# K3NG_Rotator_Interface_V2.net
KiCad netlist of a schematic drawn in EAGLE
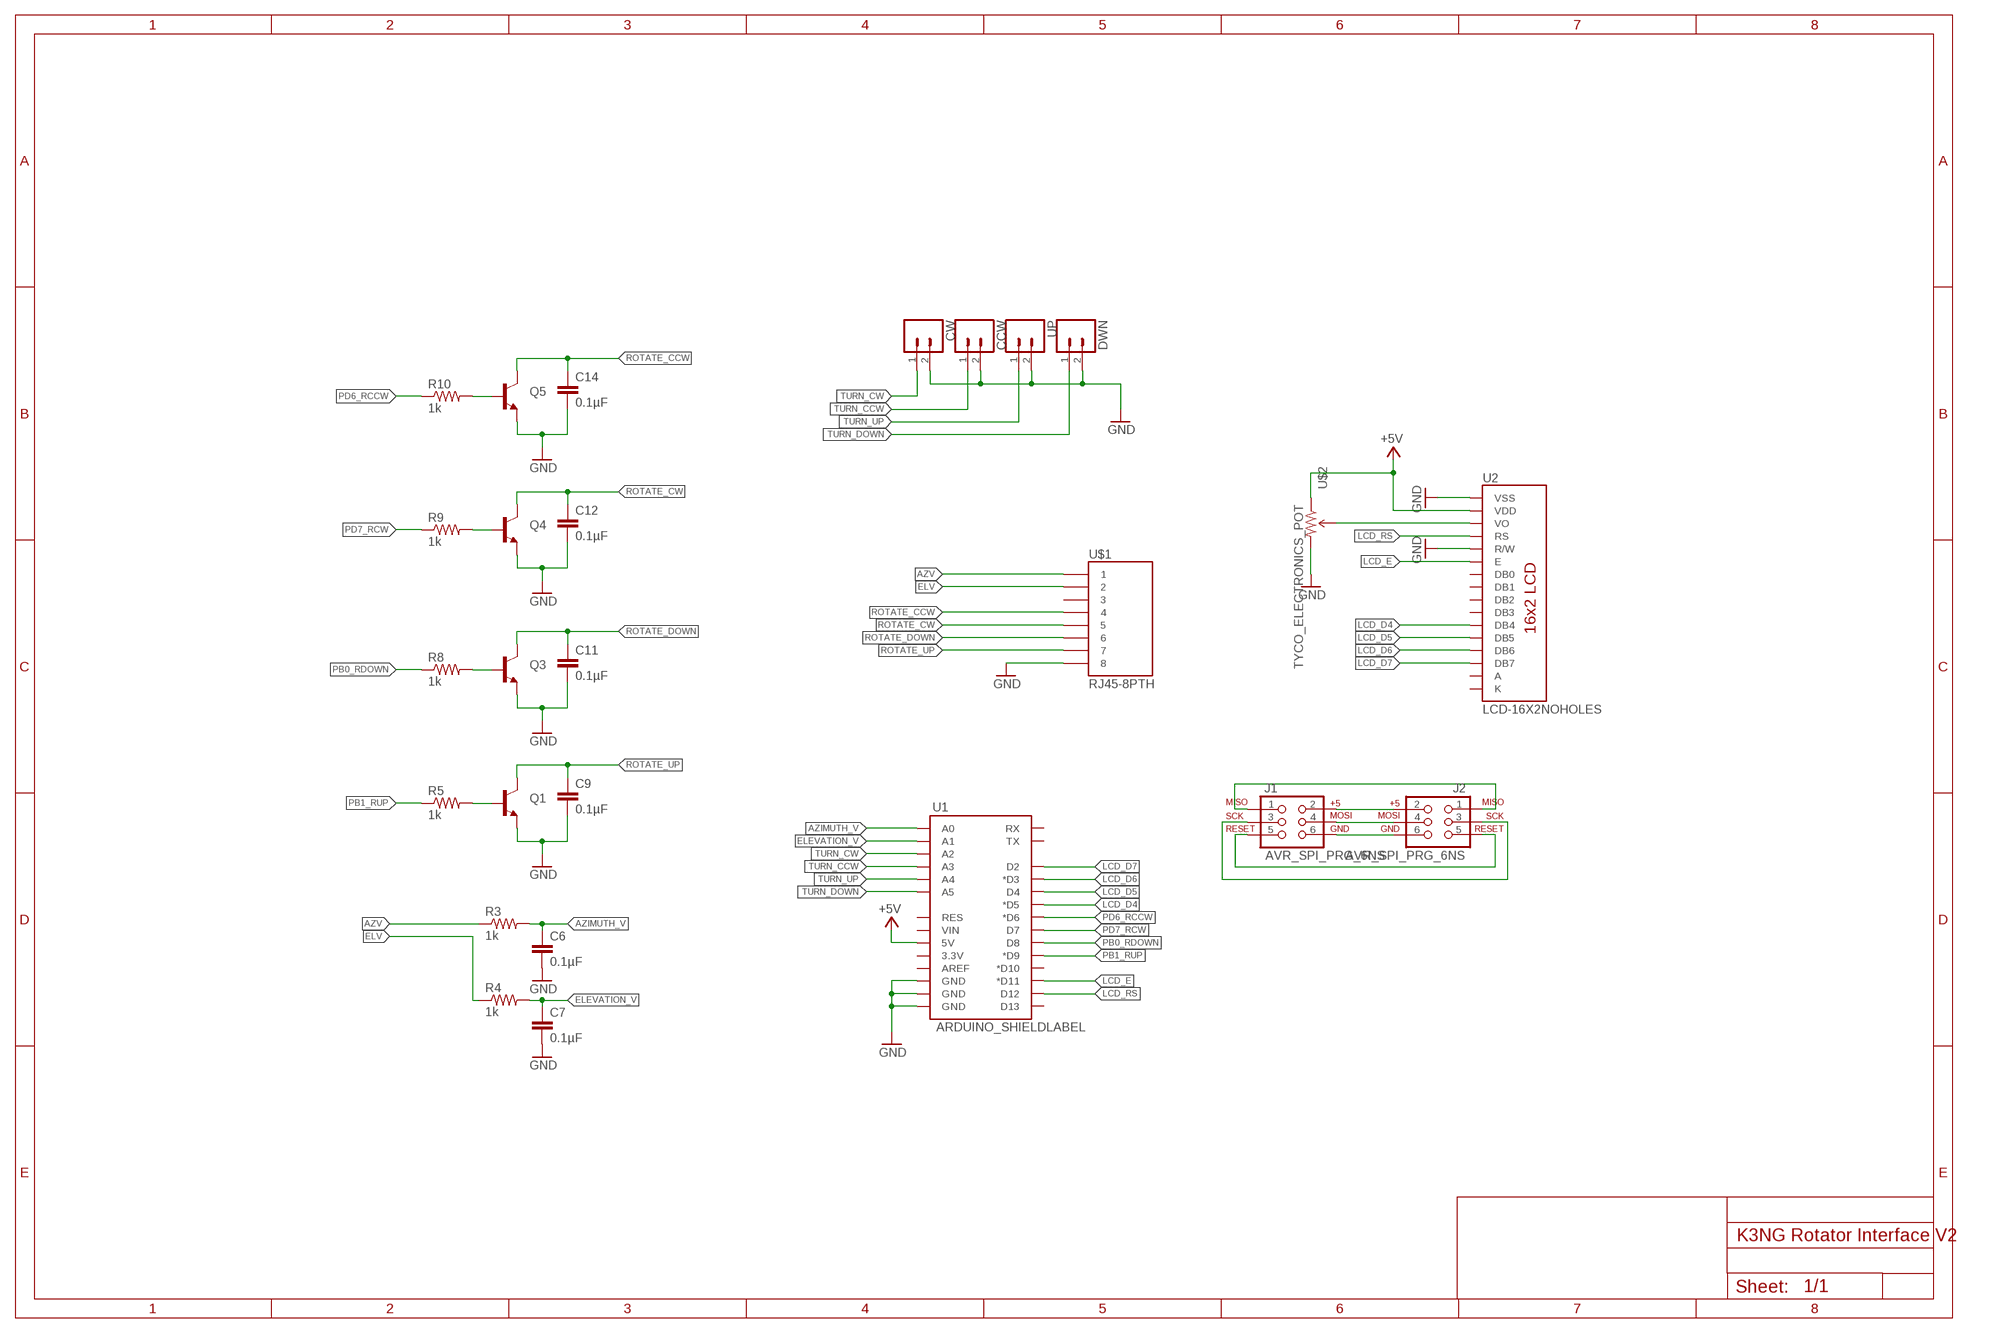
[diagram p0: schematic, sheet 1]

(export (version "E")
  (design (tool "Eeschema 10.0.6"))
  (components
    (comp (ref "C6")
      (value "0.1µF")
      (footprint "eagle-import:0603-CAP")
      (libsource (lib "eagle-import") (part "CAP0603-CAP"))
    )
    (comp (ref "C7")
      (value "0.1µF")
      (footprint "eagle-import:0603-CAP")
      (libsource (lib "eagle-import") (part "CAP0603-CAP"))
    )
    (comp (ref "C9")
      (value "0.1µF")
      (footprint "eagle-import:0603-CAP")
      (libsource (lib "eagle-import") (part "CAP0603-CAP"))
    )
    (comp (ref "C11")
      (value "0.1µF")
      (footprint "eagle-import:0603-CAP")
      (libsource (lib "eagle-import") (part "CAP0603-CAP"))
    )
    (comp (ref "C12")
      (value "0.1µF")
      (footprint "eagle-import:0603-CAP")
      (libsource (lib "eagle-import") (part "CAP0603-CAP"))
    )
    (comp (ref "C14")
      (value "0.1µF")
      (footprint "eagle-import:0603-CAP")
      (libsource (lib "eagle-import") (part "CAP0603-CAP"))
    )
    (comp (ref "CCW")
      (value "M02PTH")
      (footprint "eagle-import:1X02")
      (libsource (lib "eagle-import") (part "M02PTH"))
    )
    (comp (ref "CW")
      (value "M02PTH")
      (footprint "eagle-import:1X02")
      (libsource (lib "eagle-import") (part "M02PTH"))
    )
    (comp (ref "DWN")
      (value "M02PTH")
      (footprint "eagle-import:1X02")
      (libsource (lib "eagle-import") (part "M02PTH"))
    )
    (comp (ref "J1")
      (value "AVR_SPI_PRG_6NS")
      (footprint "eagle-import:2X3-NS")
      (libsource (lib "eagle-import") (part "AVR_SPI_PRG_6NS"))
    )
    (comp (ref "J2")
      (value "AVR_SPI_PRG_6NS")
      (footprint "eagle-import:2X3-NS")
      (libsource (lib "eagle-import") (part "AVR_SPI_PRG_6NS"))
    )
    (comp (ref "Q1")
      (value "TRANSISTOR_NPNSOT23")
      (footprint "eagle-import:SOT23")
      (libsource (lib "eagle-import") (part "TRANSISTOR_NPNSOT23"))
    )
    (comp (ref "Q3")
      (value "TRANSISTOR_NPNSOT23")
      (footprint "eagle-import:SOT23")
      (libsource (lib "eagle-import") (part "TRANSISTOR_NPNSOT23"))
    )
    (comp (ref "Q4")
      (value "TRANSISTOR_NPNSOT23")
      (footprint "eagle-import:SOT23")
      (libsource (lib "eagle-import") (part "TRANSISTOR_NPNSOT23"))
    )
    (comp (ref "Q5")
      (value "TRANSISTOR_NPNSOT23")
      (footprint "eagle-import:SOT23")
      (libsource (lib "eagle-import") (part "TRANSISTOR_NPNSOT23"))
    )
    (comp (ref "R3")
      (value "1k")
      (footprint "eagle-import:0805")
      (libsource (lib "eagle-import") (part "RESISTOR0805-RES"))
    )
    (comp (ref "R4")
      (value "1k")
      (footprint "eagle-import:0805")
      (libsource (lib "eagle-import") (part "RESISTOR0805-RES"))
    )
    (comp (ref "R5")
      (value "1k")
      (footprint "eagle-import:0805")
      (libsource (lib "eagle-import") (part "RESISTOR0805-RES"))
    )
    (comp (ref "R8")
      (value "1k")
      (footprint "eagle-import:0805")
      (libsource (lib "eagle-import") (part "RESISTOR0805-RES"))
    )
    (comp (ref "R9")
      (value "1k")
      (footprint "eagle-import:0805")
      (libsource (lib "eagle-import") (part "RESISTOR0805-RES"))
    )
    (comp (ref "R10")
      (value "1k")
      (footprint "eagle-import:0805")
      (libsource (lib "eagle-import") (part "RESISTOR0805-RES"))
    )
    (comp (ref "U$1")
      (value "RJ45-8PTH")
      (footprint "eagle-import:RJ45-8")
      (libsource (lib "eagle-import") (part "RJ45-8PTH"))
    )
    (comp (ref "U$2")
      (value "TYCO_ELECTRONICS_POT")
      (footprint "eagle-import:TYCO_ELECTRONICS_POT")
      (libsource (lib "eagle-import") (part "TYCO_ELECTRONICS_POT"))
    )
    (comp (ref "U1")
      (value "ARDUINO_SHIELDLABEL")
      (footprint "eagle-import:DUEMILANOVE_SHIELD")
      (libsource (lib "eagle-import") (part "ARDUINO_SHIELDLABEL"))
    )
    (comp (ref "U2")
      (value "LCD-16X2NOHOLES")
      (footprint "eagle-import:LCD-16X2_NOHOLES")
      (libsource (lib "eagle-import") (part "LCD-16X2NOHOLES"))
    )
    (comp (ref "UP")
      (value "M02PTH")
      (footprint "eagle-import:1X02")
      (libsource (lib "eagle-import") (part "M02PTH"))
    )
  )
  (nets
    (net (code "1") (name "+5V") (class "Default")
      (node (ref "U$2") (pin "P$1") (pinfunction "CCW_P$1") (pintype "passive"))
      (node (ref "U1") (pin "5V") (pinfunction "5V_5V") (pintype "bidirectional"))
      (node (ref "U2") (pin "2") (pinfunction "VDD_2") (pintype "power_in"))
    )
    (net (code "2") (name "/A") (class "Default")
      (node (ref "U2") (pin "15") (pinfunction "A_15") (pintype "power_in"))
    )
    (net (code "3") (name "/K") (class "Default")
      (node (ref "U2") (pin "16") (pinfunction "K_16") (pintype "power_in"))
    )
    (net (code "4") (name "AZIMUTH_V") (class "Default")
      (node (ref "C6") (pin "1") (pinfunction "1_1") (pintype "passive"))
      (node (ref "R3") (pin "2") (pinfunction "2_2") (pintype "passive"))
      (node (ref "U1") (pin "A0") (pinfunction "A0_A0") (pintype "bidirectional"))
    )
    (net (code "5") (name "AZV") (class "Default")
      (node (ref "R3") (pin "1") (pinfunction "1_1") (pintype "passive"))
      (node (ref "U$1") (pin "1") (pinfunction "1_1") (pintype "bidirectional"))
    )
    (net (code "6") (name "ELEVATION_V") (class "Default")
      (node (ref "C7") (pin "1") (pinfunction "1_1") (pintype "passive"))
      (node (ref "R4") (pin "2") (pinfunction "2_2") (pintype "passive"))
      (node (ref "U1") (pin "A1") (pinfunction "A1_A1") (pintype "bidirectional"))
    )
    (net (code "7") (name "ELV") (class "Default")
      (node (ref "R4") (pin "1") (pinfunction "1_1") (pintype "passive"))
      (node (ref "U$1") (pin "2") (pinfunction "2_2") (pintype "bidirectional"))
    )
    (net (code "8") (name "GND") (class "Default")
      (node (ref "C11") (pin "2") (pinfunction "2_2") (pintype "passive"))
      (node (ref "C12") (pin "2") (pinfunction "2_2") (pintype "passive"))
      (node (ref "C14") (pin "2") (pinfunction "2_2") (pintype "passive"))
      (node (ref "C6") (pin "2") (pinfunction "2_2") (pintype "passive"))
      (node (ref "C7") (pin "2") (pinfunction "2_2") (pintype "passive"))
      (node (ref "C9") (pin "2") (pinfunction "2_2") (pintype "passive"))
      (node (ref "CCW") (pin "2") (pinfunction "2_2") (pintype "passive"))
      (node (ref "CW") (pin "2") (pinfunction "2_2") (pintype "passive"))
      (node (ref "DWN") (pin "2") (pinfunction "2_2") (pintype "passive"))
      (node (ref "Q1") (pin "2") (pinfunction "E_2") (pintype "passive"))
      (node (ref "Q3") (pin "2") (pinfunction "E_2") (pintype "passive"))
      (node (ref "Q4") (pin "2") (pinfunction "E_2") (pintype "passive"))
      (node (ref "Q5") (pin "2") (pinfunction "E_2") (pintype "passive"))
      (node (ref "U$1") (pin "8") (pinfunction "8_8") (pintype "bidirectional"))
      (node (ref "U$2") (pin "P$3") (pinfunction "CW_P$3") (pintype "passive"))
      (node (ref "U1") (pin "GND@0") (pinfunction "GND_GND@0") (pintype "bidirectional"))
      (node (ref "U1") (pin "GND@1") (pinfunction "GND_GND@1") (pintype "bidirectional"))
      (node (ref "U1") (pin "GND@2") (pinfunction "GND_GND@2") (pintype "bidirectional"))
      (node (ref "U2") (pin "1") (pinfunction "VSS_1") (pintype "power_in"))
      (node (ref "U2") (pin "5") (pinfunction "R/W_5") (pintype "input"))
      (node (ref "UP") (pin "2") (pinfunction "2_2") (pintype "passive"))
    )
    (net (code "9") (name "LCD_D4") (class "Default")
      (node (ref "U1") (pin "D5") (pinfunction "*D5_D5") (pintype "bidirectional"))
      (node (ref "U2") (pin "11") (pinfunction "DB4_11") (pintype "bidirectional"))
    )
    (net (code "10") (name "LCD_D5") (class "Default")
      (node (ref "U1") (pin "D4") (pinfunction "D4_D4") (pintype "bidirectional"))
      (node (ref "U2") (pin "12") (pinfunction "DB5_12") (pintype "bidirectional"))
    )
    (net (code "11") (name "LCD_D6") (class "Default")
      (node (ref "U1") (pin "D3") (pinfunction "*D3_D3") (pintype "bidirectional"))
      (node (ref "U2") (pin "13") (pinfunction "DB6_13") (pintype "bidirectional"))
    )
    (net (code "12") (name "LCD_D7") (class "Default")
      (node (ref "U1") (pin "D2") (pinfunction "D2_D2") (pintype "bidirectional"))
      (node (ref "U2") (pin "14") (pinfunction "DB7_14") (pintype "bidirectional"))
    )
    (net (code "13") (name "LCD_E") (class "Default")
      (node (ref "U1") (pin "D11") (pinfunction "*D11_D11") (pintype "bidirectional"))
      (node (ref "U2") (pin "6") (pinfunction "E_6") (pintype "input"))
    )
    (net (code "14") (name "LCD_RS") (class "Default")
      (node (ref "U1") (pin "D12") (pinfunction "D12_D12") (pintype "bidirectional"))
      (node (ref "U2") (pin "4") (pinfunction "RS_4") (pintype "input"))
    )
    (net (code "15") (name "Net-(J1-Pad1)") (class "Default")
      (node (ref "J1") (pin "1") (pinfunction "1_1") (pintype "passive"))
      (node (ref "J2") (pin "1") (pinfunction "1_1") (pintype "passive"))
    )
    (net (code "16") (name "Net-(J1-Pad2)") (class "Default")
      (node (ref "J1") (pin "2") (pinfunction "2_2") (pintype "passive"))
      (node (ref "J2") (pin "2") (pinfunction "2_2") (pintype "passive"))
    )
    (net (code "17") (name "Net-(J1-Pad3)") (class "Default")
      (node (ref "J1") (pin "3") (pinfunction "3_3") (pintype "passive"))
      (node (ref "J2") (pin "3") (pinfunction "3_3") (pintype "passive"))
    )
    (net (code "18") (name "Net-(J1-Pad4)") (class "Default")
      (node (ref "J1") (pin "4") (pinfunction "4_4") (pintype "passive"))
      (node (ref "J2") (pin "4") (pinfunction "4_4") (pintype "passive"))
    )
    (net (code "19") (name "Net-(J1-Pad5)") (class "Default")
      (node (ref "J1") (pin "5") (pinfunction "5_5") (pintype "passive"))
      (node (ref "J2") (pin "5") (pinfunction "5_5") (pintype "passive"))
    )
    (net (code "20") (name "Net-(J1-Pad6)") (class "Default")
      (node (ref "J1") (pin "6") (pinfunction "6_6") (pintype "passive"))
      (node (ref "J2") (pin "6") (pinfunction "6_6") (pintype "passive"))
    )
    (net (code "21") (name "Net-(Q1-B)") (class "Default")
      (node (ref "Q1") (pin "1") (pinfunction "B_1") (pintype "passive"))
      (node (ref "R5") (pin "2") (pinfunction "2_2") (pintype "passive"))
    )
    (net (code "22") (name "Net-(Q3-B)") (class "Default")
      (node (ref "Q3") (pin "1") (pinfunction "B_1") (pintype "passive"))
      (node (ref "R8") (pin "2") (pinfunction "2_2") (pintype "passive"))
    )
    (net (code "23") (name "Net-(Q4-B)") (class "Default")
      (node (ref "Q4") (pin "1") (pinfunction "B_1") (pintype "passive"))
      (node (ref "R9") (pin "2") (pinfunction "2_2") (pintype "passive"))
    )
    (net (code "24") (name "Net-(Q5-B)") (class "Default")
      (node (ref "Q5") (pin "1") (pinfunction "B_1") (pintype "passive"))
      (node (ref "R10") (pin "2") (pinfunction "2_2") (pintype "passive"))
    )
    (net (code "25") (name "Net-(U$2-WIPER)") (class "Default")
      (node (ref "U$2") (pin "P$2") (pinfunction "WIPER_P$2") (pintype "passive"))
      (node (ref "U2") (pin "3") (pinfunction "VO_3") (pintype "bidirectional"))
    )
    (net (code "26") (name "PB0_RDOWN") (class "Default")
      (node (ref "R8") (pin "1") (pinfunction "1_1") (pintype "passive"))
      (node (ref "U1") (pin "D8") (pinfunction "D8_D8") (pintype "bidirectional"))
    )
    (net (code "27") (name "PB1_RUP") (class "Default")
      (node (ref "R5") (pin "1") (pinfunction "1_1") (pintype "passive"))
      (node (ref "U1") (pin "D9") (pinfunction "*D9_D9") (pintype "bidirectional"))
    )
    (net (code "28") (name "PD6_RCCW") (class "Default")
      (node (ref "R10") (pin "1") (pinfunction "1_1") (pintype "passive"))
      (node (ref "U1") (pin "D6") (pinfunction "*D6_D6") (pintype "bidirectional"))
    )
    (net (code "29") (name "PD7_RCW") (class "Default")
      (node (ref "R9") (pin "1") (pinfunction "1_1") (pintype "passive"))
      (node (ref "U1") (pin "D7") (pinfunction "D7_D7") (pintype "bidirectional"))
    )
    (net (code "30") (name "ROTATE_CCW") (class "Default")
      (node (ref "C14") (pin "1") (pinfunction "1_1") (pintype "passive"))
      (node (ref "Q5") (pin "3") (pinfunction "C_3") (pintype "passive"))
      (node (ref "U$1") (pin "4") (pinfunction "4_4") (pintype "bidirectional"))
    )
    (net (code "31") (name "ROTATE_CW") (class "Default")
      (node (ref "C12") (pin "1") (pinfunction "1_1") (pintype "passive"))
      (node (ref "Q4") (pin "3") (pinfunction "C_3") (pintype "passive"))
      (node (ref "U$1") (pin "5") (pinfunction "5_5") (pintype "bidirectional"))
    )
    (net (code "32") (name "ROTATE_DOWN") (class "Default")
      (node (ref "C11") (pin "1") (pinfunction "1_1") (pintype "passive"))
      (node (ref "Q3") (pin "3") (pinfunction "C_3") (pintype "passive"))
      (node (ref "U$1") (pin "6") (pinfunction "6_6") (pintype "bidirectional"))
    )
    (net (code "33") (name "ROTATE_UP") (class "Default")
      (node (ref "C9") (pin "1") (pinfunction "1_1") (pintype "passive"))
      (node (ref "Q1") (pin "3") (pinfunction "C_3") (pintype "passive"))
      (node (ref "U$1") (pin "7") (pinfunction "7_7") (pintype "bidirectional"))
    )
    (net (code "34") (name "TURN_CCW") (class "Default")
      (node (ref "CCW") (pin "1") (pinfunction "1_1") (pintype "passive"))
      (node (ref "U1") (pin "A3") (pinfunction "A3_A3") (pintype "bidirectional"))
    )
    (net (code "35") (name "TURN_CW") (class "Default")
      (node (ref "CW") (pin "1") (pinfunction "1_1") (pintype "passive"))
      (node (ref "U1") (pin "A2") (pinfunction "A2_A2") (pintype "bidirectional"))
    )
    (net (code "36") (name "TURN_DOWN") (class "Default")
      (node (ref "DWN") (pin "1") (pinfunction "1_1") (pintype "passive"))
      (node (ref "U1") (pin "A5") (pinfunction "A5_A5") (pintype "bidirectional"))
    )
    (net (code "37") (name "TURN_UP") (class "Default")
      (node (ref "U1") (pin "A4") (pinfunction "A4_A4") (pintype "bidirectional"))
      (node (ref "UP") (pin "1") (pinfunction "1_1") (pintype "passive"))
    )
    (net (code "38") (name "unconnected-(U$1-Pad3)") (class "Default")
      (node (ref "U$1") (pin "3") (pinfunction "3_3") (pintype "bidirectional"))
    )
    (net (code "39") (name "unconnected-(U1-*D10-PadD10)") (class "Default")
      (node (ref "U1") (pin "D10") (pinfunction "*D10_D10") (pintype "bidirectional"))
    )
    (net (code "40") (name "unconnected-(U1-Pad3.3V)") (class "Default")
      (node (ref "U1") (pin "3.3V") (pinfunction "3.3V_3.3V") (pintype "bidirectional"))
    )
    (net (code "41") (name "unconnected-(U1-PadAREF)") (class "Default")
      (node (ref "U1") (pin "AREF") (pinfunction "AREF_AREF") (pintype "bidirectional"))
    )
    (net (code "42") (name "unconnected-(U1-PadD13)") (class "Default")
      (node (ref "U1") (pin "D13") (pinfunction "D13_D13") (pintype "bidirectional"))
    )
    (net (code "43") (name "unconnected-(U1-PadRES)") (class "Default")
      (node (ref "U1") (pin "RES") (pinfunction "RES_RES") (pintype "bidirectional"))
    )
    (net (code "44") (name "unconnected-(U1-PadRX)") (class "Default")
      (node (ref "U1") (pin "RX") (pinfunction "RX_RX") (pintype "bidirectional"))
    )
    (net (code "45") (name "unconnected-(U1-PadTX)") (class "Default")
      (node (ref "U1") (pin "TX") (pinfunction "TX_TX") (pintype "bidirectional"))
    )
    (net (code "46") (name "unconnected-(U1-PadVIN)") (class "Default")
      (node (ref "U1") (pin "VIN") (pinfunction "VIN_VIN") (pintype "bidirectional"))
    )
    (net (code "47") (name "unconnected-(U2-DB0-Pad7)") (class "Default")
      (node (ref "U2") (pin "7") (pinfunction "DB0_7") (pintype "bidirectional"))
    )
    (net (code "48") (name "unconnected-(U2-DB1-Pad8)") (class "Default")
      (node (ref "U2") (pin "8") (pinfunction "DB1_8") (pintype "bidirectional"))
    )
    (net (code "49") (name "unconnected-(U2-DB2-Pad9)") (class "Default")
      (node (ref "U2") (pin "9") (pinfunction "DB2_9") (pintype "bidirectional"))
    )
    (net (code "50") (name "unconnected-(U2-DB3-Pad10)") (class "Default")
      (node (ref "U2") (pin "10") (pinfunction "DB3_10") (pintype "bidirectional"))
    )
  )
)
